# Ex_Controller.net
KiCad netlist of a schematic drawn in EAGLE
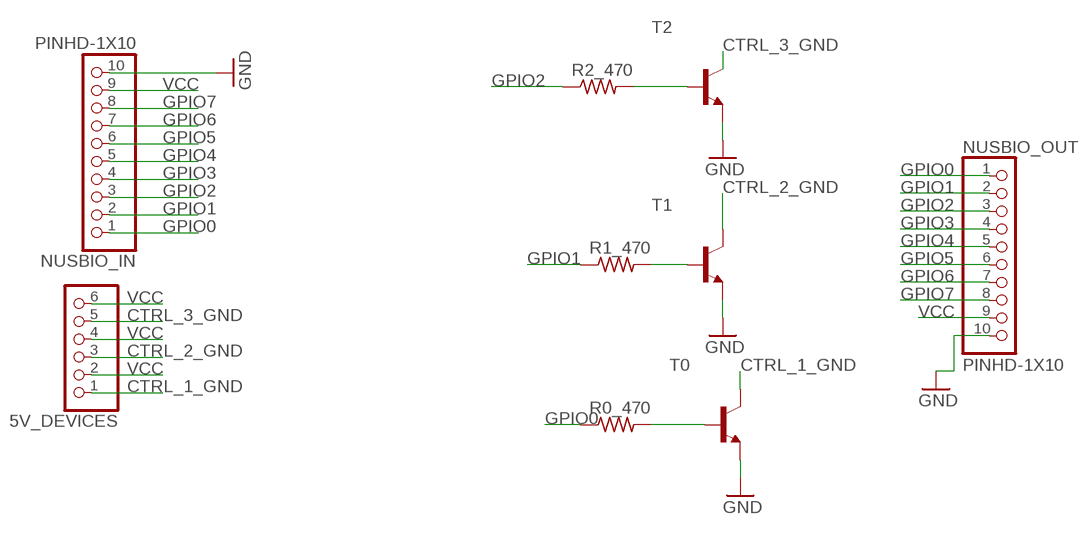
[diagram p0: schematic, sheet 1]

(export (version "E")
  (design (tool "Eeschema 10.0.6"))
  (components
    (comp (ref "5V_DEVICES")
      (value "PINHD-1X6")
      (footprint "eagle-import:1X06")
      (libsource (lib "eagle-import") (part "PINHD-1X6"))
    )
    (comp (ref "NUSBIO_IN")
      (value "PINHD-1X10")
      (footprint "eagle-import:1X10-BIG")
      (libsource (lib "eagle-import") (part "PINHD-1X10"))
    )
    (comp (ref "NUSBIO_OUT")
      (value "PINHD-1X10")
      (footprint "eagle-import:1X10-BIG")
      (libsource (lib "eagle-import") (part "PINHD-1X10"))
    )
    (comp (ref "R0_470")
      (value "R-US_R0805")
      (footprint "eagle-import:R0805")
      (libsource (lib "eagle-import") (part "R-US_R0805"))
    )
    (comp (ref "R1_470")
      (value "R-US_R0805")
      (footprint "eagle-import:R0805")
      (libsource (lib "eagle-import") (part "R-US_R0805"))
    )
    (comp (ref "R2_470")
      (value "R-US_R0805")
      (footprint "eagle-import:R0805")
      (libsource (lib "eagle-import") (part "R-US_R0805"))
    )
    (comp (ref "T0")
      (value "MMBT3904LT1-NPN-SOT23-BEC")
      (footprint "eagle-import:SOT23-BEC")
      (libsource (lib "eagle-import") (part "-NPN-SOT23-BECMMBT3904LT1"))
    )
    (comp (ref "T1")
      (value "MMBT3904LT1-NPN-SOT23-BEC")
      (footprint "eagle-import:SOT23-BEC")
      (libsource (lib "eagle-import") (part "-NPN-SOT23-BECMMBT3904LT1"))
    )
    (comp (ref "T2")
      (value "MMBT3904LT1-NPN-SOT23-BEC")
      (footprint "eagle-import:SOT23-BEC")
      (libsource (lib "eagle-import") (part "-NPN-SOT23-BECMMBT3904LT1"))
    )
  )
  (nets
    (net (code "1") (name "/CTRL_1_GND") (class "Default")
      (node (ref "5V_DEVICES") (pin "1") (pinfunction "1_1") (pintype "passive"))
      (node (ref "T0") (pin "C") (pinfunction "C_C") (pintype "passive"))
    )
    (net (code "2") (name "/CTRL_2_GND") (class "Default")
      (node (ref "5V_DEVICES") (pin "3") (pinfunction "3_3") (pintype "passive"))
      (node (ref "T1") (pin "C") (pinfunction "C_C") (pintype "passive"))
    )
    (net (code "3") (name "/CTRL_3_GND") (class "Default")
      (node (ref "5V_DEVICES") (pin "5") (pinfunction "5_5") (pintype "passive"))
      (node (ref "T2") (pin "C") (pinfunction "C_C") (pintype "passive"))
    )
    (net (code "4") (name "/GPIO0") (class "Default")
      (node (ref "NUSBIO_IN") (pin "1") (pinfunction "1_1") (pintype "passive"))
      (node (ref "NUSBIO_OUT") (pin "1") (pinfunction "1_1") (pintype "passive"))
      (node (ref "R0_470") (pin "1") (pinfunction "1_1") (pintype "passive"))
    )
    (net (code "5") (name "/GPIO1") (class "Default")
      (node (ref "NUSBIO_IN") (pin "2") (pinfunction "2_2") (pintype "passive"))
      (node (ref "NUSBIO_OUT") (pin "2") (pinfunction "2_2") (pintype "passive"))
      (node (ref "R1_470") (pin "1") (pinfunction "1_1") (pintype "passive"))
    )
    (net (code "6") (name "/GPIO2") (class "Default")
      (node (ref "NUSBIO_IN") (pin "3") (pinfunction "3_3") (pintype "passive"))
      (node (ref "NUSBIO_OUT") (pin "3") (pinfunction "3_3") (pintype "passive"))
      (node (ref "R2_470") (pin "1") (pinfunction "1_1") (pintype "passive"))
    )
    (net (code "7") (name "/GPIO3") (class "Default")
      (node (ref "NUSBIO_IN") (pin "4") (pinfunction "4_4") (pintype "passive"))
      (node (ref "NUSBIO_OUT") (pin "4") (pinfunction "4_4") (pintype "passive"))
    )
    (net (code "8") (name "/GPIO4") (class "Default")
      (node (ref "NUSBIO_IN") (pin "5") (pinfunction "5_5") (pintype "passive"))
      (node (ref "NUSBIO_OUT") (pin "5") (pinfunction "5_5") (pintype "passive"))
    )
    (net (code "9") (name "/GPIO5") (class "Default")
      (node (ref "NUSBIO_IN") (pin "6") (pinfunction "6_6") (pintype "passive"))
      (node (ref "NUSBIO_OUT") (pin "6") (pinfunction "6_6") (pintype "passive"))
    )
    (net (code "10") (name "/GPIO6") (class "Default")
      (node (ref "NUSBIO_IN") (pin "7") (pinfunction "7_7") (pintype "passive"))
      (node (ref "NUSBIO_OUT") (pin "7") (pinfunction "7_7") (pintype "passive"))
    )
    (net (code "11") (name "/GPIO7") (class "Default")
      (node (ref "NUSBIO_IN") (pin "8") (pinfunction "8_8") (pintype "passive"))
      (node (ref "NUSBIO_OUT") (pin "8") (pinfunction "8_8") (pintype "passive"))
    )
    (net (code "12") (name "/VCC") (class "Default")
      (node (ref "5V_DEVICES") (pin "2") (pinfunction "2_2") (pintype "passive"))
      (node (ref "5V_DEVICES") (pin "4") (pinfunction "4_4") (pintype "passive"))
      (node (ref "5V_DEVICES") (pin "6") (pinfunction "6_6") (pintype "passive"))
      (node (ref "NUSBIO_IN") (pin "9") (pinfunction "9_9") (pintype "passive"))
      (node (ref "NUSBIO_OUT") (pin "9") (pinfunction "9_9") (pintype "passive"))
    )
    (net (code "13") (name "GND") (class "Default")
      (node (ref "NUSBIO_IN") (pin "10") (pinfunction "10_10") (pintype "passive"))
      (node (ref "NUSBIO_OUT") (pin "10") (pinfunction "10_10") (pintype "passive"))
      (node (ref "T0") (pin "E") (pinfunction "E_E") (pintype "passive"))
      (node (ref "T1") (pin "E") (pinfunction "E_E") (pintype "passive"))
      (node (ref "T2") (pin "E") (pinfunction "E_E") (pintype "passive"))
    )
    (net (code "14") (name "Net-(R0_470-Pad2)") (class "Default")
      (node (ref "R0_470") (pin "2") (pinfunction "2_2") (pintype "passive"))
      (node (ref "T0") (pin "B") (pinfunction "B_B") (pintype "passive"))
    )
    (net (code "15") (name "Net-(R1_470-Pad2)") (class "Default")
      (node (ref "R1_470") (pin "2") (pinfunction "2_2") (pintype "passive"))
      (node (ref "T1") (pin "B") (pinfunction "B_B") (pintype "passive"))
    )
    (net (code "16") (name "Net-(R2_470-Pad2)") (class "Default")
      (node (ref "R2_470") (pin "2") (pinfunction "2_2") (pintype "passive"))
      (node (ref "T2") (pin "B") (pinfunction "B_B") (pintype "passive"))
    )
  )
)
